# SCH_ProMicro_evo2_v2_2025-11-15.net
KiCad netlist of a schematic drawn in EasyEDA
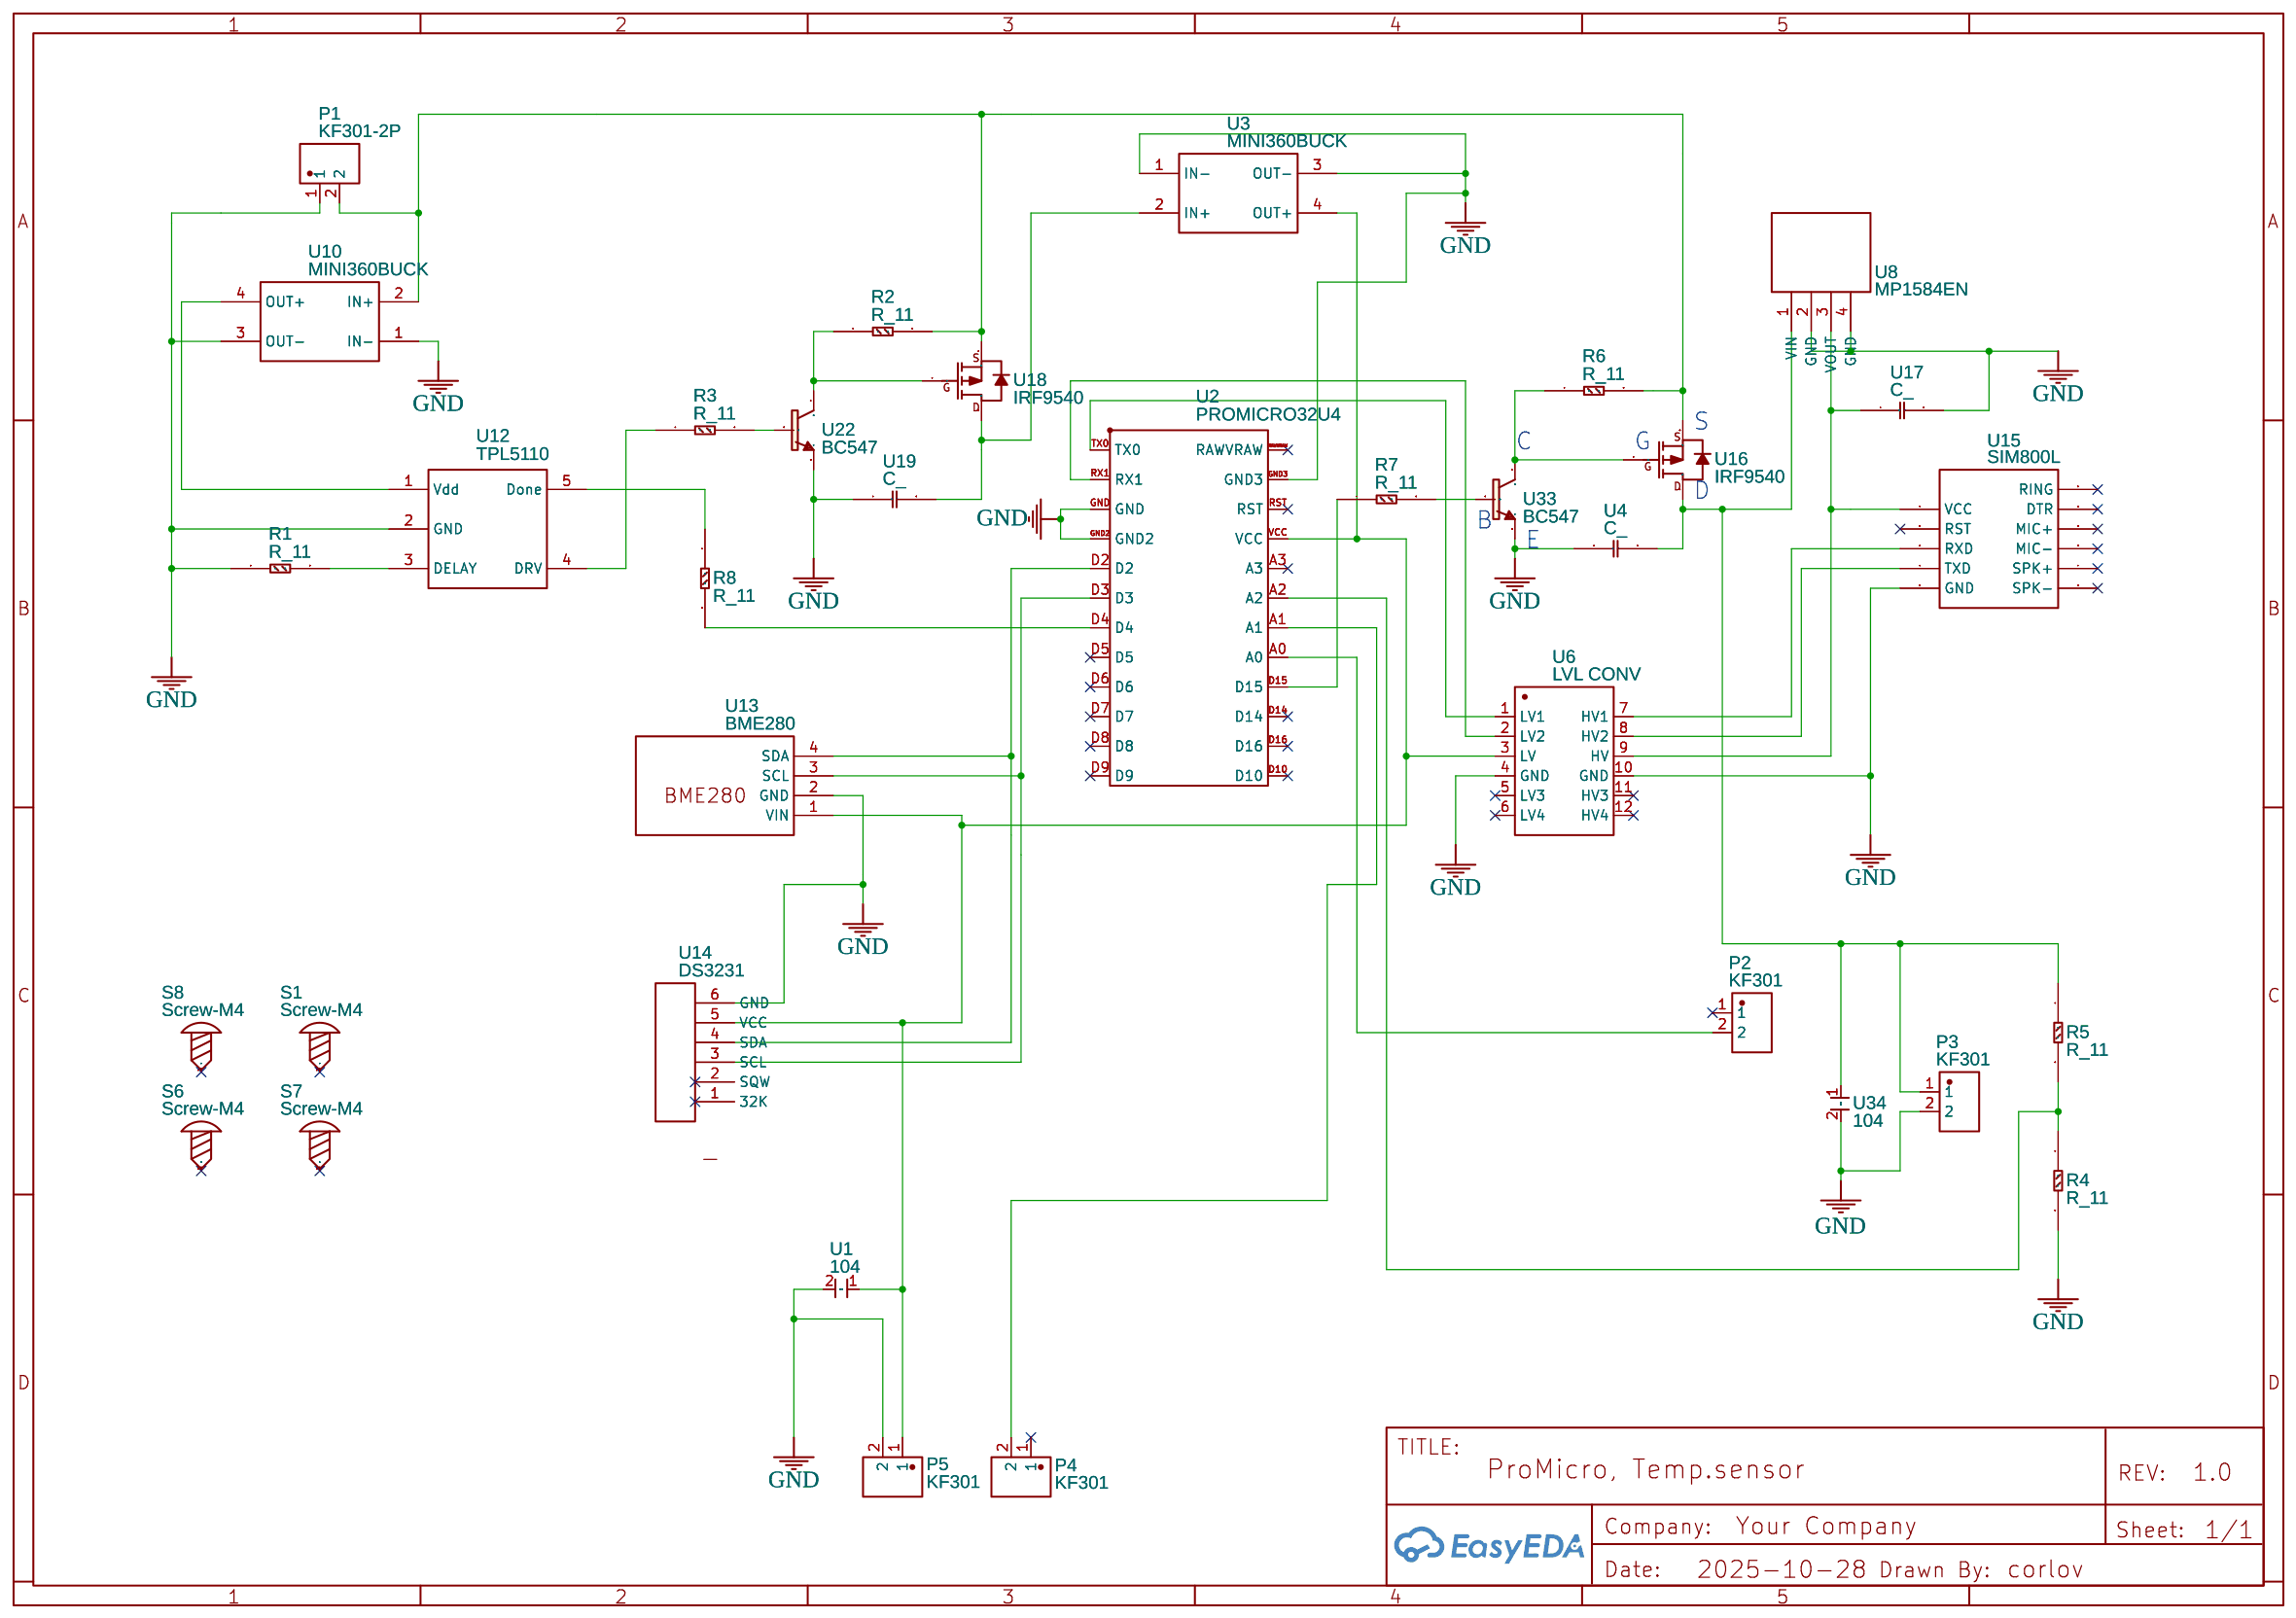
[diagram p0: schematic sheet]

(export (version "E")
  (design (tool "Eeschema 10.0.6"))
  (components
    (comp (ref "P1")
      (value "KF301-2P")
      (fields (field (name "Manufacturer Part") "KF301-2P接线端子"))
      (libsource (lib "") (part "KF301-2P VCC Y GND_2"))
    )
    (comp (ref "P2")
      (value "KF301")
      (fields (field (name "Manufacturer Part") "KF301-2P接线端子"))
      (libsource (lib "") (part "KF301-2P VCC Y GND_1"))
    )
    (comp (ref "P3")
      (value "KF301")
      (fields (field (name "Manufacturer Part") "KF301-2P接线端子"))
      (libsource (lib "") (part "KF301-2P VCC Y GND_1"))
    )
    (comp (ref "P4")
      (value "KF301")
      (fields (field (name "Manufacturer Part") "KF301-2P接线端子"))
      (libsource (lib "") (part "KF301-2P VCC Y GND"))
    )
    (comp (ref "P5")
      (value "KF301")
      (fields (field (name "Manufacturer Part") "KF301-2P接线端子"))
      (libsource (lib "") (part "KF301-2P VCC Y GND"))
    )
    (comp (ref "R1") (value "R_11") (libsource (lib "") (part "R__1")))
    (comp (ref "R2") (value "R_11") (libsource (lib "") (part "R__1")))
    (comp (ref "R3") (value "R_11") (libsource (lib "") (part "R__1")))
    (comp (ref "R4") (value "R_11") (libsource (lib "") (part "R_")))
    (comp (ref "R5") (value "R_11") (libsource (lib "") (part "R_")))
    (comp (ref "R6") (value "R_11") (libsource (lib "") (part "R__1")))
    (comp (ref "R7") (value "R_11") (libsource (lib "") (part "R__1")))
    (comp (ref "R8") (value "R_11") (libsource (lib "") (part "R_")))
    (comp (ref "S1") (value "Screw-M4") (libsource (lib "") (part "Screw-M4")))
    (comp (ref "S6") (value "Screw-M4") (libsource (lib "") (part "Screw-M4")))
    (comp (ref "S7") (value "Screw-M4") (libsource (lib "") (part "Screw-M4")))
    (comp (ref "S8") (value "Screw-M4") (libsource (lib "") (part "Screw-M4")))
    (comp (ref "U1")
      (value "104")
      (fields (field (name "Manufacturer") "Fe"))
      (libsource (lib "") (part "104_1"))
    )
    (comp (ref "U2") (value "PROMICRO32U4") (libsource (lib "") (part "PROMICRO32U4")))
    (comp (ref "U3")
      (value "MINI360BUCK")
      (fields (field (name "Manufacturer Part") "Mini360"))
      (libsource (lib "") (part "MINI360BUCK_1"))
    )
    (comp (ref "U4") (value "C_") (libsource (lib "") (part "C_")))
    (comp (ref "U6")
      (value "LVL CONV")
      (fields (field (name "Manufacturer Part") "Level Converter 4"))
      (libsource (lib "") (part "LEVEL CONVERTER 4"))
    )
    (comp (ref "U8") (value "MP1584EN") (libsource (lib "") (part "MP1584EN")))
    (comp (ref "U10")
      (value "MINI360BUCK")
      (fields (field (name "Manufacturer Part") "Mini360"))
      (libsource (lib "") (part "MINI360BUCK"))
    )
    (comp (ref "U12")
      (value "TPL5110")
      (fields (field (name "Manufacturer Part") "3435"))
      (libsource (lib "") (part "ADAFRUIT TPL5110 BREAKOUT"))
    )
    (comp (ref "U13") (value "BME280") (libsource (lib "") (part "BME280")))
    (comp (ref "U14") (value "DS3231") (libsource (lib "") (part "DS3231 upright")))
    (comp (ref "U15") (value "SIM800L") (libsource (lib "") (part "SIM800L")))
    (comp (ref "U16") (value "IRF9540") (libsource (lib "") (part "IRF9540")))
    (comp (ref "U17") (value "C_") (libsource (lib "") (part "C_")))
    (comp (ref "U18") (value "IRF9540") (libsource (lib "") (part "IRF9540")))
    (comp (ref "U19") (value "C_") (libsource (lib "") (part "C_")))
    (comp (ref "U22") (value "BC547") (libsource (lib "") (part "BC547")))
    (comp (ref "U33") (value "BC547") (libsource (lib "") (part "BC547")))
    (comp (ref "U34")
      (value "104")
      (fields (field (name "Manufacturer") "Fe"))
      (libsource (lib "") (part "104"))
    )
  )
  (nets
    (net (code "1") (name "GND") (class "Default")
      (node (ref "P1") (pin "1") (pinfunction "1_1") (pintype "unspecified"))
      (node (ref "P3") (pin "2") (pinfunction "2_2") (pintype "unspecified"))
      (node (ref "P5") (pin "2") (pinfunction "2_2") (pintype "unspecified"))
      (node (ref "R1") (pin "1") (pinfunction "1_1") (pintype "unspecified"))
      (node (ref "R4") (pin "2") (pinfunction "2_2") (pintype "unspecified"))
      (node (ref "U1") (pin "2") (pinfunction "2_2") (pintype "unspecified"))
      (node (ref "U10") (pin "1") (pinfunction "IN-_1") (pintype "unspecified"))
      (node (ref "U10") (pin "3") (pinfunction "OUT-_3") (pintype "unspecified"))
      (node (ref "U12") (pin "2") (pinfunction "GND_2") (pintype "unspecified"))
      (node (ref "U13") (pin "2") (pinfunction "GND_2") (pintype "unspecified"))
      (node (ref "U14") (pin "6") (pinfunction "GND_6") (pintype "unspecified"))
      (node (ref "U15") (pin "5") (pinfunction "GND_5") (pintype "unspecified"))
      (node (ref "U17") (pin "2") (pinfunction "2_2") (pintype "unspecified"))
      (node (ref "U19") (pin "1") (pinfunction "1_1") (pintype "unspecified"))
      (node (ref "U2") (pin "GND") (pinfunction "GND_GND") (pintype "unspecified"))
      (node (ref "U2") (pin "GND2") (pinfunction "GND2_GND2") (pintype "unspecified"))
      (node (ref "U2") (pin "GND3") (pinfunction "GND3_GND3") (pintype "unspecified"))
      (node (ref "U22") (pin "3") (pinfunction "E_3") (pintype "unspecified"))
      (node (ref "U3") (pin "1") (pinfunction "IN-_1") (pintype "unspecified"))
      (node (ref "U3") (pin "3") (pinfunction "OUT-_3") (pintype "unspecified"))
      (node (ref "U33") (pin "3") (pinfunction "E_3") (pintype "unspecified"))
      (node (ref "U34") (pin "2") (pinfunction "2_2") (pintype "unspecified"))
      (node (ref "U4") (pin "1") (pinfunction "1_1") (pintype "unspecified"))
      (node (ref "U6") (pin "10") (pinfunction "GND_10") (pintype "unspecified"))
      (node (ref "U6") (pin "4") (pinfunction "GND_4") (pintype "unspecified"))
      (node (ref "U8") (pin "2") (pinfunction "GND_2") (pintype "unspecified"))
      (node (ref "U8") (pin "4") (pinfunction "GND_4") (pintype "unspecified"))
    )
    (net (code "2") (name "Net-(P2-Pad2)") (class "Default")
      (node (ref "P2") (pin "2") (pinfunction "2_2") (pintype "unspecified"))
      (node (ref "U2") (pin "A0") (pinfunction "A0_A0") (pintype "unspecified"))
    )
    (net (code "3") (name "Net-(P4-Pad2)") (class "Default")
      (node (ref "P4") (pin "2") (pinfunction "2_2") (pintype "unspecified"))
      (node (ref "U2") (pin "A1") (pinfunction "A1_A1") (pintype "unspecified"))
    )
    (net (code "4") (name "Net-(R4-Pad1)") (class "Default")
      (node (ref "R4") (pin "1") (pinfunction "1_1") (pintype "unspecified"))
      (node (ref "R5") (pin "2") (pinfunction "2_2") (pintype "unspecified"))
      (node (ref "U2") (pin "A2") (pinfunction "A2_A2") (pintype "unspecified"))
    )
    (net (code "5") (name "Net-(R7-Pad1)") (class "Default")
      (node (ref "R7") (pin "1") (pinfunction "1_1") (pintype "unspecified"))
      (node (ref "U2") (pin "D15") (pinfunction "D15_D15") (pintype "unspecified"))
    )
    (net (code "6") (name "Net-(R8-Pad2)") (class "Default")
      (node (ref "R8") (pin "2") (pinfunction "2_2") (pintype "unspecified"))
      (node (ref "U2") (pin "D4") (pinfunction "D4_D4") (pintype "unspecified"))
    )
    (net (code "7") (name "Net-(U6-LV1)") (class "Default")
      (node (ref "U2") (pin "TX0") (pinfunction "TX0_TX0") (pintype "unspecified"))
      (node (ref "U6") (pin "1") (pinfunction "LV1_1") (pintype "unspecified"))
    )
    (net (code "8") (name "Net-(U6-LV2)") (class "Default")
      (node (ref "U2") (pin "RX1") (pinfunction "RX1_RX1") (pintype "unspecified"))
      (node (ref "U6") (pin "2") (pinfunction "LV2_2") (pintype "unspecified"))
    )
    (net (code "9") (name "Net-(U10-IN+)") (class "Default")
      (node (ref "P1") (pin "2") (pinfunction "2_2") (pintype "unspecified"))
      (node (ref "R2") (pin "2") (pinfunction "2_2") (pintype "unspecified"))
      (node (ref "R6") (pin "2") (pinfunction "2_2") (pintype "unspecified"))
      (node (ref "U10") (pin "2") (pinfunction "IN+_2") (pintype "unspecified"))
      (node (ref "U16") (pin "3") (pinfunction "S_3") (pintype "unspecified"))
      (node (ref "U18") (pin "3") (pinfunction "S_3") (pintype "unspecified"))
    )
    (net (code "10") (name "Net-(U10-OUT+)") (class "Default")
      (node (ref "U10") (pin "4") (pinfunction "OUT+_4") (pintype "unspecified"))
      (node (ref "U12") (pin "1") (pinfunction "Vdd_1") (pintype "unspecified"))
    )
    (net (code "11") (name "Net-(U12-DELAY)") (class "Default")
      (node (ref "R1") (pin "2") (pinfunction "2_2") (pintype "unspecified"))
      (node (ref "U12") (pin "3") (pinfunction "DELAY_3") (pintype "unspecified"))
    )
    (net (code "12") (name "Net-(U12-DRV)") (class "Default")
      (node (ref "R3") (pin "1") (pinfunction "1_1") (pintype "unspecified"))
      (node (ref "U12") (pin "4") (pinfunction "DRV_4") (pintype "unspecified"))
    )
    (net (code "13") (name "Net-(U12-Done)") (class "Default")
      (node (ref "R8") (pin "1") (pinfunction "1_1") (pintype "unspecified"))
      (node (ref "U12") (pin "5") (pinfunction "Done_5") (pintype "unspecified"))
    )
    (net (code "14") (name "Net-(U13-SCL)") (class "Default")
      (node (ref "U13") (pin "3") (pinfunction "SCL_3") (pintype "unspecified"))
      (node (ref "U14") (pin "3") (pinfunction "SCL_3") (pintype "unspecified"))
      (node (ref "U2") (pin "D3") (pinfunction "D3_D3") (pintype "unspecified"))
    )
    (net (code "15") (name "Net-(U13-SDA)") (class "Default")
      (node (ref "U13") (pin "4") (pinfunction "SDA_4") (pintype "unspecified"))
      (node (ref "U14") (pin "4") (pinfunction "SDA_4") (pintype "unspecified"))
      (node (ref "U2") (pin "D2") (pinfunction "D2_D2") (pintype "unspecified"))
    )
    (net (code "16") (name "Net-(U13-VIN)") (class "Default")
      (node (ref "P5") (pin "1") (pinfunction "1_1") (pintype "unspecified"))
      (node (ref "U1") (pin "1") (pinfunction "1_1") (pintype "unspecified"))
      (node (ref "U13") (pin "1") (pinfunction "VIN_1") (pintype "unspecified"))
      (node (ref "U14") (pin "5") (pinfunction "VCC_5") (pintype "unspecified"))
      (node (ref "U2") (pin "VCC") (pinfunction "VCC_VCC") (pintype "unspecified"))
      (node (ref "U3") (pin "4") (pinfunction "OUT+_4") (pintype "unspecified"))
      (node (ref "U6") (pin "3") (pinfunction "LV_3") (pintype "unspecified"))
    )
    (net (code "17") (name "Net-(U15-RXD)") (class "Default")
      (node (ref "U15") (pin "3") (pinfunction "RXD_3") (pintype "unspecified"))
      (node (ref "U6") (pin "7") (pinfunction "HV1_7") (pintype "unspecified"))
    )
    (net (code "18") (name "Net-(U15-TXD)") (class "Default")
      (node (ref "U15") (pin "4") (pinfunction "TXD_4") (pintype "unspecified"))
      (node (ref "U6") (pin "8") (pinfunction "HV2_8") (pintype "unspecified"))
    )
    (net (code "19") (name "Net-(U15-VCC)") (class "Default")
      (node (ref "U15") (pin "1") (pinfunction "VCC_1") (pintype "unspecified"))
      (node (ref "U17") (pin "1") (pinfunction "1_1") (pintype "unspecified"))
      (node (ref "U6") (pin "9") (pinfunction "HV_9") (pintype "unspecified"))
      (node (ref "U8") (pin "3") (pinfunction "VOUT_3") (pintype "unspecified"))
    )
    (net (code "20") (name "Net-(U16-D)") (class "Default")
      (node (ref "P3") (pin "1") (pinfunction "1_1") (pintype "unspecified"))
      (node (ref "R5") (pin "1") (pinfunction "1_1") (pintype "unspecified"))
      (node (ref "U16") (pin "2") (pinfunction "D_2") (pintype "unspecified"))
      (node (ref "U34") (pin "1") (pinfunction "1_1") (pintype "unspecified"))
      (node (ref "U4") (pin "2") (pinfunction "2_2") (pintype "unspecified"))
      (node (ref "U8") (pin "1") (pinfunction "VIN_1") (pintype "unspecified"))
    )
    (net (code "21") (name "Net-(U16-G)") (class "Default")
      (node (ref "R6") (pin "1") (pinfunction "1_1") (pintype "unspecified"))
      (node (ref "U16") (pin "1") (pinfunction "G_1") (pintype "unspecified"))
      (node (ref "U33") (pin "1") (pinfunction "C_1") (pintype "unspecified"))
    )
    (net (code "22") (name "Net-(U18-D)") (class "Default")
      (node (ref "U18") (pin "2") (pinfunction "D_2") (pintype "unspecified"))
      (node (ref "U19") (pin "2") (pinfunction "2_2") (pintype "unspecified"))
      (node (ref "U3") (pin "2") (pinfunction "IN+_2") (pintype "unspecified"))
    )
    (net (code "23") (name "Net-(U18-G)") (class "Default")
      (node (ref "R2") (pin "1") (pinfunction "1_1") (pintype "unspecified"))
      (node (ref "U18") (pin "1") (pinfunction "G_1") (pintype "unspecified"))
      (node (ref "U22") (pin "1") (pinfunction "C_1") (pintype "unspecified"))
    )
    (net (code "24") (name "Net-(U22-B)") (class "Default")
      (node (ref "R3") (pin "2") (pinfunction "2_2") (pintype "unspecified"))
      (node (ref "U22") (pin "2") (pinfunction "B_2") (pintype "unspecified"))
    )
    (net (code "25") (name "Net-(U33-B)") (class "Default")
      (node (ref "R7") (pin "2") (pinfunction "2_2") (pintype "unspecified"))
      (node (ref "U33") (pin "2") (pinfunction "B_2") (pintype "unspecified"))
    )
    (net (code "26") (name "unconnected-(P2-Pad1)") (class "Default")
      (node (ref "P2") (pin "1") (pinfunction "1_1") (pintype "unspecified+no_connect"))
    )
    (net (code "27") (name "unconnected-(P4-Pad1)") (class "Default")
      (node (ref "P4") (pin "1") (pinfunction "1_1") (pintype "unspecified+no_connect"))
    )
    (net (code "28") (name "unconnected-(S1-Pad1)") (class "Default")
      (node (ref "S1") (pin "1") (pinfunction "1_1") (pintype "unspecified+no_connect"))
    )
    (net (code "29") (name "unconnected-(S6-Pad1)") (class "Default")
      (node (ref "S6") (pin "1") (pinfunction "1_1") (pintype "unspecified+no_connect"))
    )
    (net (code "30") (name "unconnected-(S7-Pad1)") (class "Default")
      (node (ref "S7") (pin "1") (pinfunction "1_1") (pintype "unspecified+no_connect"))
    )
    (net (code "31") (name "unconnected-(S8-Pad1)") (class "Default")
      (node (ref "S8") (pin "1") (pinfunction "1_1") (pintype "unspecified+no_connect"))
    )
    (net (code "32") (name "unconnected-(U2-PadA3)") (class "Default")
      (node (ref "U2") (pin "A3") (pinfunction "A3_A3") (pintype "unspecified+no_connect"))
    )
    (net (code "33") (name "unconnected-(U2-PadD5)") (class "Default")
      (node (ref "U2") (pin "D5") (pinfunction "D5_D5") (pintype "unspecified+no_connect"))
    )
    (net (code "34") (name "unconnected-(U2-PadD6)") (class "Default")
      (node (ref "U2") (pin "D6") (pinfunction "D6_D6") (pintype "unspecified+no_connect"))
    )
    (net (code "35") (name "unconnected-(U2-PadD7)") (class "Default")
      (node (ref "U2") (pin "D7") (pinfunction "D7_D7") (pintype "unspecified+no_connect"))
    )
    (net (code "36") (name "unconnected-(U2-PadD8)") (class "Default")
      (node (ref "U2") (pin "D8") (pinfunction "D8_D8") (pintype "unspecified+no_connect"))
    )
    (net (code "37") (name "unconnected-(U2-PadD9)") (class "Default")
      (node (ref "U2") (pin "D9") (pinfunction "D9_D9") (pintype "unspecified+no_connect"))
    )
    (net (code "38") (name "unconnected-(U2-PadD10)") (class "Default")
      (node (ref "U2") (pin "D10") (pinfunction "D10_D10") (pintype "unspecified+no_connect"))
    )
    (net (code "39") (name "unconnected-(U2-PadD14)") (class "Default")
      (node (ref "U2") (pin "D14") (pinfunction "D14_D14") (pintype "unspecified+no_connect"))
    )
    (net (code "40") (name "unconnected-(U2-PadD16)") (class "Default")
      (node (ref "U2") (pin "D16") (pinfunction "D16_D16") (pintype "unspecified+no_connect"))
    )
    (net (code "41") (name "unconnected-(U2-PadRAWVRAW)") (class "Default")
      (node (ref "U2") (pin "RAWVRAW") (pinfunction "RAWVRAW_RAWVRAW") (pintype "unspecified+no_connect"))
    )
    (net (code "42") (name "unconnected-(U2-PadRST)") (class "Default")
      (node (ref "U2") (pin "RST") (pinfunction "RST_RST") (pintype "unspecified+no_connect"))
    )
    (net (code "43") (name "unconnected-(U6-HV3-Pad11)") (class "Default")
      (node (ref "U6") (pin "11") (pinfunction "HV3_11") (pintype "unspecified+no_connect"))
    )
    (net (code "44") (name "unconnected-(U6-HV4-Pad12)") (class "Default")
      (node (ref "U6") (pin "12") (pinfunction "HV4_12") (pintype "unspecified+no_connect"))
    )
    (net (code "45") (name "unconnected-(U6-LV3-Pad5)") (class "Default")
      (node (ref "U6") (pin "5") (pinfunction "LV3_5") (pintype "unspecified+no_connect"))
    )
    (net (code "46") (name "unconnected-(U6-LV4-Pad6)") (class "Default")
      (node (ref "U6") (pin "6") (pinfunction "LV4_6") (pintype "unspecified+no_connect"))
    )
    (net (code "47") (name "unconnected-(U14-32K-Pad1)") (class "Default")
      (node (ref "U14") (pin "1") (pinfunction "32K_1") (pintype "unspecified+no_connect"))
    )
    (net (code "48") (name "unconnected-(U14-SQW-Pad2)") (class "Default")
      (node (ref "U14") (pin "2") (pinfunction "SQW_2") (pintype "unspecified+no_connect"))
    )
    (net (code "49") (name "unconnected-(U15-DTR-Pad10)") (class "Default")
      (node (ref "U15") (pin "10") (pinfunction "DTR_10") (pintype "unspecified+no_connect"))
    )
    (net (code "50") (name "unconnected-(U15-MIC+-Pad9)") (class "Default")
      (node (ref "U15") (pin "9") (pinfunction "MIC+_9") (pintype "unspecified+no_connect"))
    )
    (net (code "51") (name "unconnected-(U15-MIC--Pad8)") (class "Default")
      (node (ref "U15") (pin "8") (pinfunction "MIC-_8") (pintype "unspecified+no_connect"))
    )
    (net (code "52") (name "unconnected-(U15-RING-Pad11)") (class "Default")
      (node (ref "U15") (pin "11") (pinfunction "RING_11") (pintype "unspecified+no_connect"))
    )
    (net (code "53") (name "unconnected-(U15-RST-Pad2)") (class "Default")
      (node (ref "U15") (pin "2") (pinfunction "RST_2") (pintype "unspecified+no_connect"))
    )
    (net (code "54") (name "unconnected-(U15-SPK+-Pad7)") (class "Default")
      (node (ref "U15") (pin "7") (pinfunction "SPK+_7") (pintype "unspecified+no_connect"))
    )
    (net (code "55") (name "unconnected-(U15-SPK--Pad6)") (class "Default")
      (node (ref "U15") (pin "6") (pinfunction "SPK-_6") (pintype "unspecified+no_connect"))
    )
  )
)
